# SLG46826G-breakout.net
KiCad netlist of a schematic drawn in EAGLE
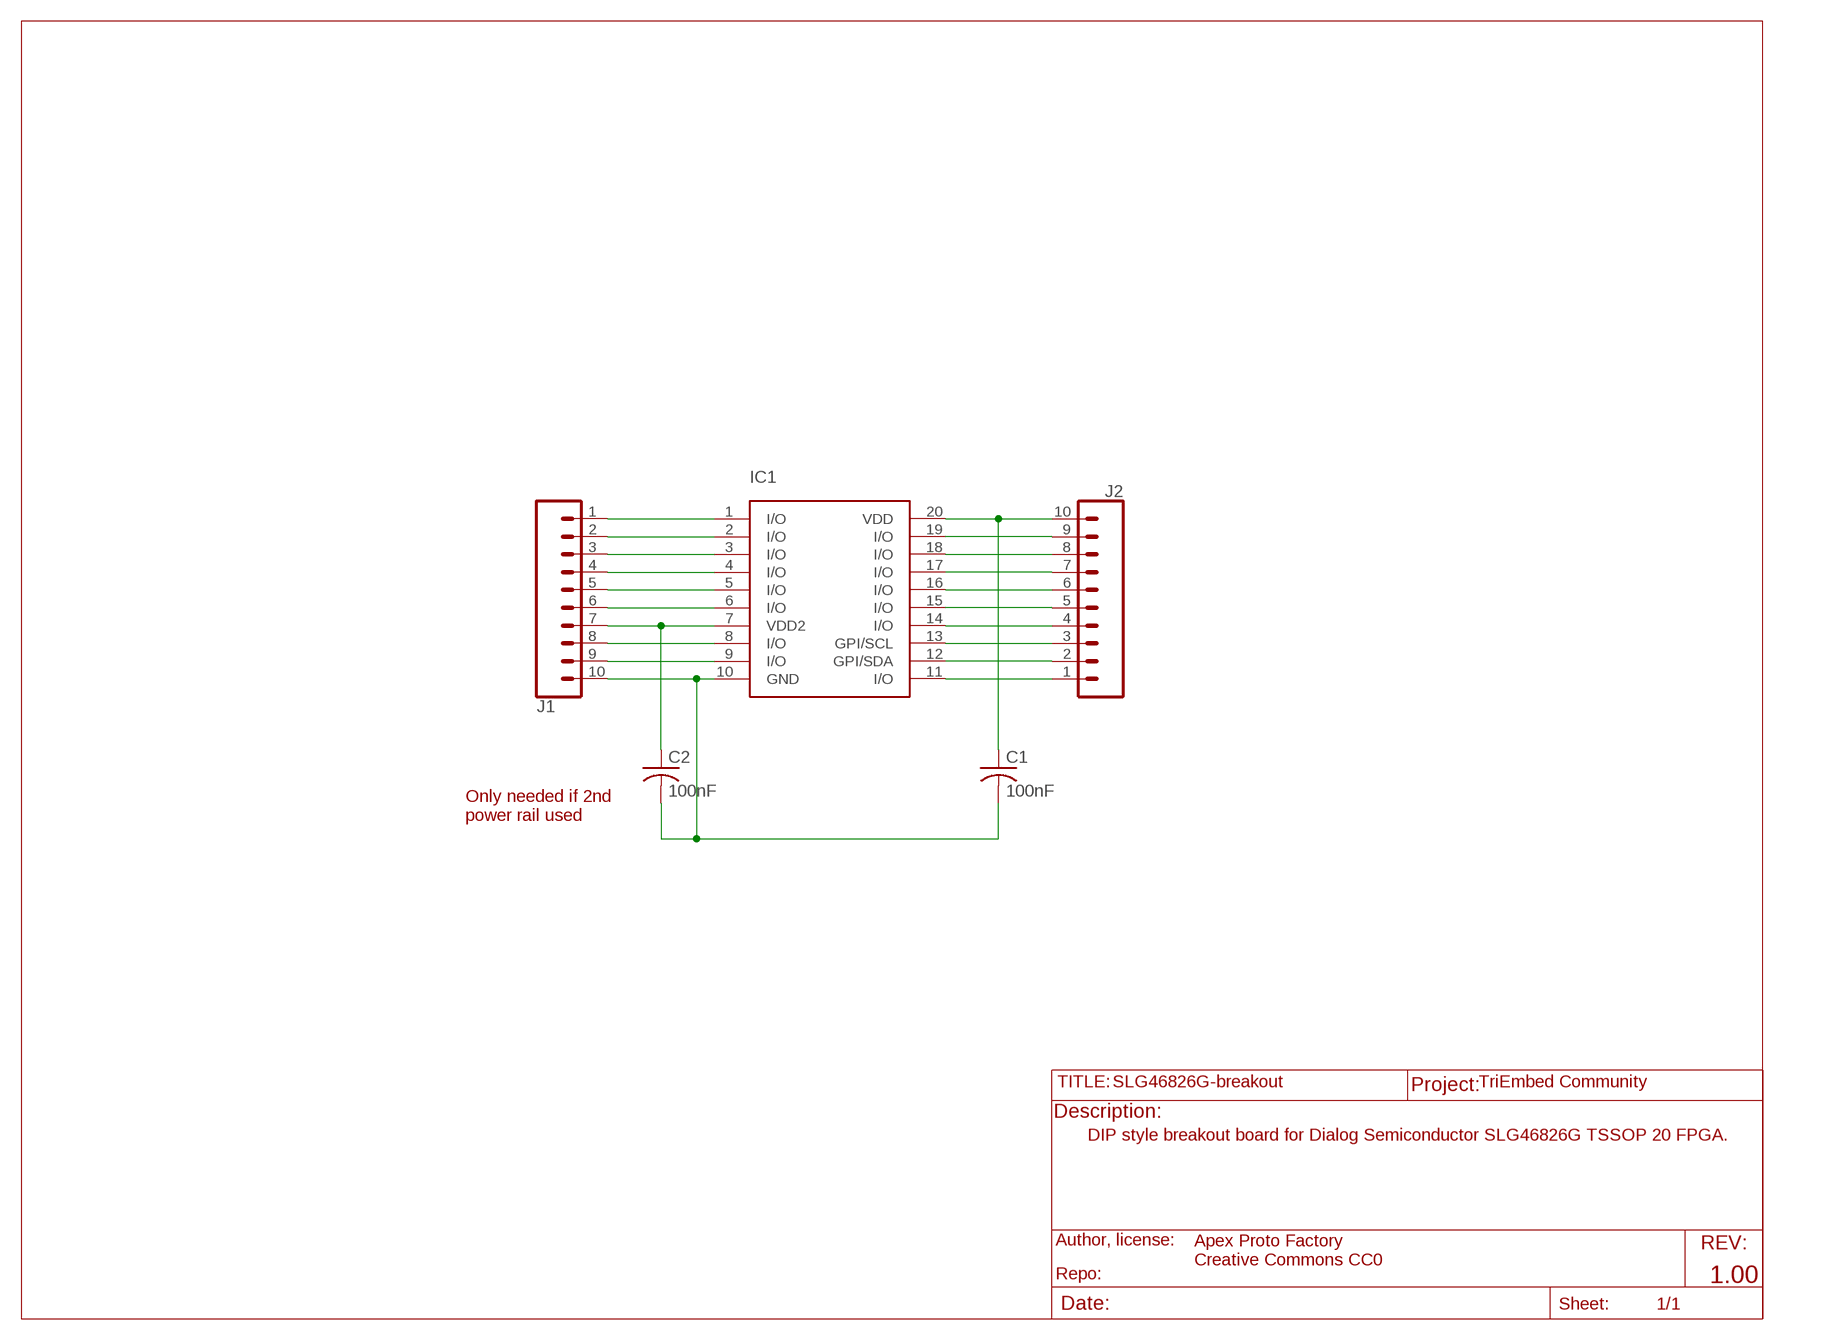
[diagram p0: schematic, sheet 1]

(export (version "E")
  (design (tool "Eeschema 10.0.6"))
  (components
    (comp (ref "C1")
      (value "100nF")
      (footprint "eagle-import:C0805")
      (libsource (lib "eagle-import") (part "C-USC0805"))
    )
    (comp (ref "C2")
      (value "100nF")
      (footprint "eagle-import:C0805")
      (libsource (lib "eagle-import") (part "C-USC0805"))
    )
    (comp (ref "IC1")
      (value "SLG46826G")
      (footprint "eagle-import:TSOP-20")
      (libsource (lib "eagle-import") (part "SLG46826G"))
    )
    (comp (ref "J1")
      (value "CONN_10\"")
      (footprint "eagle-import:1X10")
      (libsource (lib "eagle-import") (part "CONN_10{dblquote}"))
    )
    (comp (ref "J2")
      (value "CONN_10\"")
      (footprint "eagle-import:1X10")
      (libsource (lib "eagle-import") (part "CONN_10{dblquote}"))
    )
  )
  (nets
    (net (code "1") (name "Net-(IC1-GND)") (class "Default")
      (node (ref "C1") (pin "2") (pinfunction "2_2") (pintype "passive"))
      (node (ref "C2") (pin "2") (pinfunction "2_2") (pintype "passive"))
      (node (ref "IC1") (pin "10") (pinfunction "GND_10") (pintype "power_in"))
      (node (ref "J1") (pin "10") (pinfunction "10_10") (pintype "passive"))
    )
    (net (code "2") (name "Net-(IC1-GPI{slash}SCL)") (class "Default")
      (node (ref "IC1") (pin "13") (pinfunction "GPI/SCL_13") (pintype "input"))
      (node (ref "J2") (pin "3") (pinfunction "3_3") (pintype "passive"))
    )
    (net (code "3") (name "Net-(IC1-GPI{slash}SDA)") (class "Default")
      (node (ref "IC1") (pin "12") (pinfunction "GPI/SDA_12") (pintype "input"))
      (node (ref "J2") (pin "2") (pinfunction "2_2") (pintype "passive"))
    )
    (net (code "4") (name "Net-(IC1-I{slash}O-Pad1)") (class "Default")
      (node (ref "IC1") (pin "1") (pinfunction "I/O_1") (pintype "bidirectional"))
      (node (ref "J1") (pin "1") (pinfunction "1_1") (pintype "passive"))
    )
    (net (code "5") (name "Net-(IC1-I{slash}O-Pad2)") (class "Default")
      (node (ref "IC1") (pin "2") (pinfunction "I/O_2") (pintype "input"))
      (node (ref "J1") (pin "2") (pinfunction "2_2") (pintype "passive"))
    )
    (net (code "6") (name "Net-(IC1-I{slash}O-Pad3)") (class "Default")
      (node (ref "IC1") (pin "3") (pinfunction "I/O_3") (pintype "bidirectional"))
      (node (ref "J1") (pin "3") (pinfunction "3_3") (pintype "passive"))
    )
    (net (code "7") (name "Net-(IC1-I{slash}O-Pad4)") (class "Default")
      (node (ref "IC1") (pin "4") (pinfunction "I/O_4") (pintype "bidirectional"))
      (node (ref "J1") (pin "4") (pinfunction "4_4") (pintype "passive"))
    )
    (net (code "8") (name "Net-(IC1-I{slash}O-Pad5)") (class "Default")
      (node (ref "IC1") (pin "5") (pinfunction "I/O_5") (pintype "bidirectional"))
      (node (ref "J1") (pin "5") (pinfunction "5_5") (pintype "passive"))
    )
    (net (code "9") (name "Net-(IC1-I{slash}O-Pad6)") (class "Default")
      (node (ref "IC1") (pin "6") (pinfunction "I/O_6") (pintype "bidirectional"))
      (node (ref "J1") (pin "6") (pinfunction "6_6") (pintype "passive"))
    )
    (net (code "10") (name "Net-(IC1-I{slash}O-Pad8)") (class "Default")
      (node (ref "IC1") (pin "8") (pinfunction "I/O_8") (pintype "bidirectional"))
      (node (ref "J1") (pin "8") (pinfunction "8_8") (pintype "passive"))
    )
    (net (code "11") (name "Net-(IC1-I{slash}O-Pad9)") (class "Default")
      (node (ref "IC1") (pin "9") (pinfunction "I/O_9") (pintype "bidirectional"))
      (node (ref "J1") (pin "9") (pinfunction "9_9") (pintype "passive"))
    )
    (net (code "12") (name "Net-(IC1-I{slash}O-Pad11)") (class "Default")
      (node (ref "IC1") (pin "11") (pinfunction "I/O_11") (pintype "bidirectional"))
      (node (ref "J2") (pin "1") (pinfunction "1_1") (pintype "passive"))
    )
    (net (code "13") (name "Net-(IC1-I{slash}O-Pad14)") (class "Default")
      (node (ref "IC1") (pin "14") (pinfunction "I/O_14") (pintype "bidirectional"))
      (node (ref "J2") (pin "4") (pinfunction "4_4") (pintype "passive"))
    )
    (net (code "14") (name "Net-(IC1-I{slash}O-Pad15)") (class "Default")
      (node (ref "IC1") (pin "15") (pinfunction "I/O_15") (pintype "bidirectional"))
      (node (ref "J2") (pin "5") (pinfunction "5_5") (pintype "passive"))
    )
    (net (code "15") (name "Net-(IC1-I{slash}O-Pad16)") (class "Default")
      (node (ref "IC1") (pin "16") (pinfunction "I/O_16") (pintype "bidirectional"))
      (node (ref "J2") (pin "6") (pinfunction "6_6") (pintype "passive"))
    )
    (net (code "16") (name "Net-(IC1-I{slash}O-Pad17)") (class "Default")
      (node (ref "IC1") (pin "17") (pinfunction "I/O_17") (pintype "bidirectional"))
      (node (ref "J2") (pin "7") (pinfunction "7_7") (pintype "passive"))
    )
    (net (code "17") (name "Net-(IC1-I{slash}O-Pad18)") (class "Default")
      (node (ref "IC1") (pin "18") (pinfunction "I/O_18") (pintype "bidirectional"))
      (node (ref "J2") (pin "8") (pinfunction "8_8") (pintype "passive"))
    )
    (net (code "18") (name "Net-(IC1-I{slash}O-Pad19)") (class "Default")
      (node (ref "IC1") (pin "19") (pinfunction "I/O_19") (pintype "output"))
      (node (ref "J2") (pin "9") (pinfunction "9_9") (pintype "passive"))
    )
    (net (code "19") (name "Net-(IC1-VDD)") (class "Default")
      (node (ref "C1") (pin "1") (pinfunction "1_1") (pintype "passive"))
      (node (ref "IC1") (pin "20") (pinfunction "VDD_20") (pintype "power_in"))
      (node (ref "J2") (pin "10") (pinfunction "10_10") (pintype "passive"))
    )
    (net (code "20") (name "Net-(IC1-VDD2)") (class "Default")
      (node (ref "C2") (pin "1") (pinfunction "1_1") (pintype "passive"))
      (node (ref "IC1") (pin "7") (pinfunction "VDD2_7") (pintype "power_in"))
      (node (ref "J1") (pin "7") (pinfunction "7_7") (pintype "passive"))
    )
  )
)
